# EMG_Sensors_Power.net
KiCad netlist of a schematic drawn in Altium Designer
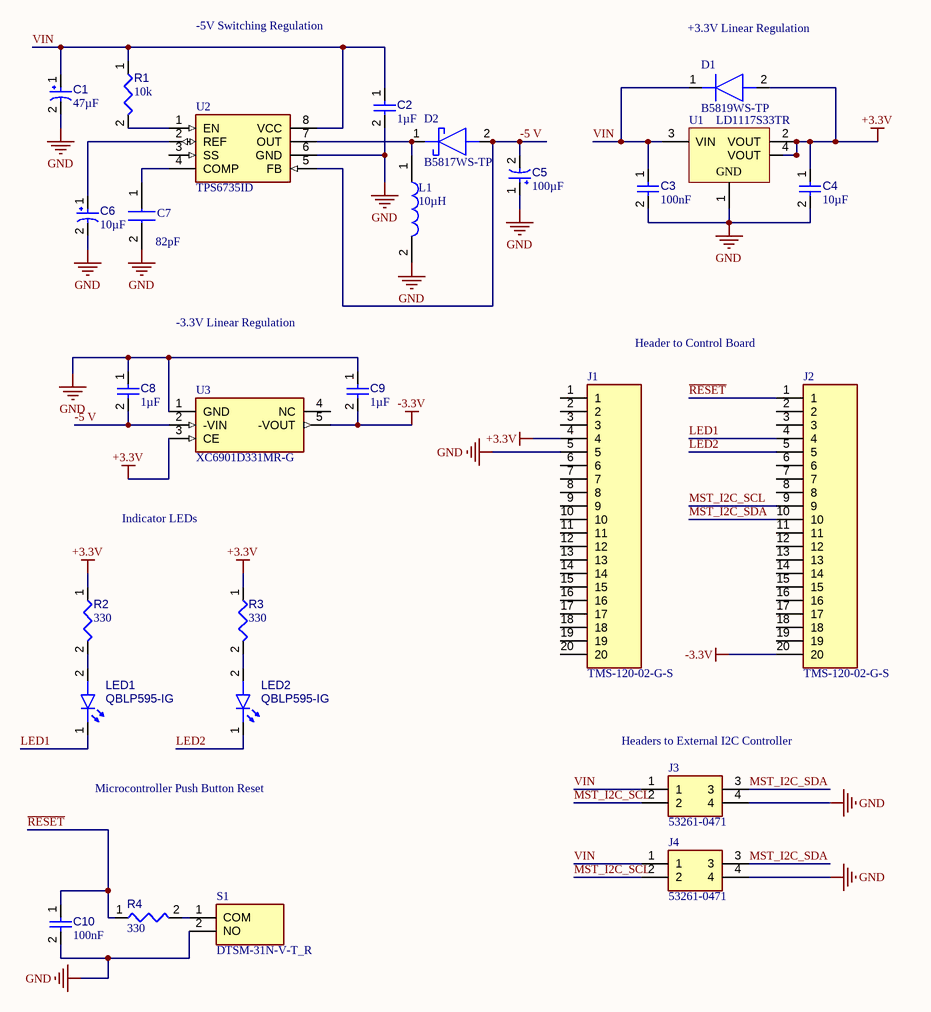
[diagram p0: EMG_Sensors_Power.SchDoc]

(export (version "E")
  (design (tool "Eeschema 10.0.6"))
  (components
    (comp (ref "C1")
      (value "47µF")
      (footprint "AVX-TAJ-C-2_L")
      (fields
        (field (name "TOLERANCE") "10%")
        (field (name "MANUFACTURER") "AVX")
        (field (name "Comment") "TAJC476K016RNJ")
      )
      (libsource (lib "Education") (part "CAP-P-2"))
    )
    (comp (ref "C2")
      (value "1µF")
      (footprint "CAPC1608X94X35NL15T15")
      (description "Chip Capacitor, 1 uF, +/- 10%, 16 V, 0603 (1608 Metric)")
      (fields (field (name "TOLERANCE") "10%") (field (name "Comment") "Capacitor 1 uF +/- 10% 16 V 0603"))
      (libsource (lib "Education") (part "CAP-NP-2"))
    )
    (comp (ref "C3")
      (value "100nF")
      (footprint "CAPC1005X56X25LL10T15")
      (description "Chip Capacitor, 0.1 uF, +/- 5%, 16 V, 0402 (1005 Metric)")
      (fields (field (name "TOLERANCE") "5%") (field (name "Comment") "Capacitor 0.1 uF +/- 5% 16 V 0402"))
      (libsource (lib "Education") (part "CAP-NP-2"))
    )
    (comp (ref "C4")
      (value "10µF")
      (footprint "CAPC2013X135X45NL10T25")
      (description "Chip Capacitor, 10 uF, +/- 10%, 16 V, 0805 (2012 Metric)")
      (fields (field (name "TOLERANCE") "10%") (field (name "Comment") "Capacitor 10 uF +/- 10% 16 V 0805"))
      (libsource (lib "Education") (part "CAP-NP-2"))
    )
    (comp (ref "C5")
      (value "100µF")
      (footprint "AVX-TAJ-C-2_L")
      (fields
        (field (name "TOLERANCE") "10%")
        (field (name "MANUFACTURER") "AVX")
        (field (name "Comment") "TAJC107K010RNJ")
      )
      (libsource (lib "") (part "CAP-P-2_1"))
    )
    (comp (ref "C6")
      (value "10µF")
      (footprint "CAPMP3217X18-T_V")
      (fields
        (field (name "TOLERANCE") "10%")
        (field (name "MANUFACTURER") "AVX")
        (field (name "Comment") "TAJA106K016RNJ")
      )
      (libsource (lib "Education") (part "CAP-P-2"))
    )
    (comp (ref "C7")
      (value "82pF")
      (footprint "SamacSys:CAPC0603X33N")
      (description "Capacitor 82pF  GRM0335C1H820JA01D")
      (fields (field (name "MANUFACTURER_PART_NUMBER") "GRM0335C1H820JA01D"))
      (libsource (lib "*") (part "GRM0335C1H820JA01D"))
    )
    (comp (ref "C8")
      (value "1µF")
      (footprint "CAPC1608X90X35ML15T15")
      (description "Chip Capacitor, 1 uF, +/- 10%, 16 V, 0603 (1608 Metric)")
      (fields (field (name "TOLERANCE") "10%") (field (name "Comment") "Capacitor 1uF +/- 10% 16V 0603"))
      (libsource (lib "Education") (part "CAP-NP-2"))
    )
    (comp (ref "C9")
      (value "1µF")
      (footprint "CAPC1608X90X35ML15T15")
      (description "Chip Capacitor, 1 uF, +/- 10%, 16 V, 0603 (1608 Metric)")
      (fields (field (name "TOLERANCE") "10%") (field (name "Comment") "Capacitor 1uF +/- 10% 16V 0603"))
      (libsource (lib "Education") (part "CAP-NP-2"))
    )
    (comp (ref "C10")
      (value "100nF")
      (footprint "CAPC1005X56X25LL10T15")
      (description "Chip Capacitor, 0.1 uF, +/- 5%, 16 V, 0402 (1005 Metric)")
      (fields (field (name "TOLERANCE") "5%") (field (name "Comment") "Capacitor 0.1 uF +/- 5% 16 V 0402"))
      (libsource (lib "Education") (part "CAP-NP-2"))
    )
    (comp (ref "D1")
      (value "B5819WS-TP")
      (footprint "SamacSys:SOD2512X115N")
      (description "Diode B5819WS-TP")
      (fields (field (name "MOUSER PART NUMBER") "833-B5819WS-TP"))
      (libsource (lib "*") (part "B5819WS-TP"))
    )
    (comp (ref "D2")
      (value "B5817WS-TP")
      (footprint "SamacSys:SOD2512X115N")
      (description "Schottky Diode B5817WS-TP")
      (fields (field (name "MOUSER PART NUMBER") "833-B5817WS-TP"))
      (libsource (lib "*") (part "B5817WS-TP"))
    )
    (comp (ref "J1")
      (value "TMS-120-02-G-S")
      (footprint "SamacSys:TMS-120-YY-XX-S")
      (description "Connector - female needed, place under board TMS-120-02-G-S")
      (fields (field (name "MOUSER PART NUMBER") "200-TMS12002GS"))
      (libsource (lib "*") (part "TMS-120-02-G-S"))
    )
    (comp (ref "J2")
      (value "TMS-120-02-G-S")
      (footprint "SamacSys:TMS-120-YY-XX-S")
      (description "Connector - female needed, place under board TMS-120-02-G-S")
      (fields (field (name "MOUSER PART NUMBER") "200-TMS12002GS"))
      (libsource (lib "*") (part "TMS-120-02-G-S"))
    )
    (comp (ref "J3")
      (value "53261-0471")
      (footprint "SamacSys:53261-0471")
      (description "Connector 53261-0471")
      (fields (field (name "MOUSER PART NUMBER") "538-53261-0471"))
      (libsource (lib "*") (part "53261-0471"))
    )
    (comp (ref "J4")
      (value "53261-0471")
      (footprint "SamacSys:53261-0471")
      (description "Connector 53261-0471")
      (fields (field (name "MOUSER PART NUMBER") "538-53261-0471"))
      (libsource (lib "*") (part "53261-0471"))
    )
    (comp (ref "L1")
      (value "10µH")
      (footprint "SamacSys:DO1608C")
      (description "Inductor 10µH DO1608C-103MLC")
      (fields
        (field (name "MANUFACTURER_PART_NUMBER") "DO1608C-103MLC")
        (field (name "MOUSER PART NUMBER") "994-DO1608C-103MLC")
      )
      (libsource (lib "*") (part "DO1608C-103MLC"))
    )
    (comp (ref "LED1")
      (value "QBLP595-IG")
      (footprint "QTB-QBLP595_V")
      (libsource (lib "Education") (part "LED-KA-2"))
    )
    (comp (ref "LED2")
      (value "QBLP595-IG")
      (footprint "QTB-QBLP595_V")
      (libsource (lib "Education") (part "LED-KA-2"))
    )
    (comp (ref "R1")
      (value "10k")
      (footprint "RESC1005X40X25ML05T05")
      (description "Chip Resistor, 10 KOhm, +/- 1%, 63 mW, -55 to 155 degC, 0402 (1005 Metric)")
      (fields (field (name "POWER") "63mW") (field (name "TOLERANCE") "1%"))
      (libsource (lib "Education") (part "RES-2"))
    )
    (comp (ref "R2")
      (value "330")
      (footprint "RESC0402(1005)_L")
      (description "Chip Resistor, 330 Ohms, +/-5 %, 63 mW, -55 to 155 degC, 0402")
      (fields (field (name "POWER") "63mW") (field (name "TOLERANCE") "5%"))
      (libsource (lib "Education") (part "RES-2"))
    )
    (comp (ref "R3")
      (value "330")
      (footprint "RESC0402(1005)_L")
      (description "Chip Resistor, 330 Ohms, +/-5 %, 63 mW, -55 to 155 degC, 0402")
      (fields (field (name "POWER") "63mW") (field (name "TOLERANCE") "5%"))
      (libsource (lib "Education") (part "RES-2"))
    )
    (comp (ref "R4")
      (value "330")
      (footprint "RESC0402(1005)_L")
      (description "Chip Resistor, 330 Ohms, +/-5 %, 63 mW, -55 to 155 degC, 0402")
      (fields (field (name "POWER") "63mW") (field (name "TOLERANCE") "5%"))
      (libsource (lib "Education") (part "RES-2"))
    )
    (comp (ref "S1")
      (value "DTSM-31N-V-T_R")
      (footprint "SamacSys:DTSM32NVTR")
      (description "Switch DTSM-31N-V-T_R")
      (fields
        (field (name "MANUFACTURER_PART_NUMBER") "DTSM-31N-V-T/R")
        (field (name "MOUSER PART NUMBER") "113-DTSM31NVTR")
      )
      (libsource (lib "SamacSys") (part "DTSM-31N-V-T_R"))
    )
    (comp (ref "U1")
      (value "LD1117S33TR")
      (footprint "SOT-223_L")
      (description "Fixed Low Drop Positive Voltage Regulator, 3.3V, 4-Pin SOT-223, Tape and Reel")
      (libsource (lib "Altium Content Vault") (part "PM-REG-LD1117-SOT4"))
    )
    (comp (ref "U2")
      (value "TPS6735ID")
      (footprint "SamacSys:SOIC127P600X175-8N")
      (description "Power Supply")
      (fields (field (name "MOUSER PART NUMBER") "595-TPS6735ID"))
      (libsource (lib "*") (part "TPS6735ID"))
    )
    (comp (ref "U3")
      (value "XC6901D331MR-G")
      (footprint "SamacSys:SOT95P280X130-5N")
      (description "Power Supply XC6901D331MR-G")
      (fields (field (name "MOUSER PART NUMBER") "865-XC6901D331MR-G"))
      (libsource (lib "*") (part "XC6901D331MR-G"))
    )
  )
  (nets
    (net (code "1") (name "+3.3V") (class "Default")
      (node (ref "C4") (pin "1") (pinfunction "1_1") (pintype "passive"))
      (node (ref "D1") (pin "2") (pinfunction "A_2") (pintype "passive"))
      (node (ref "J1") (pin "4") (pinfunction "4_4") (pintype "passive"))
      (node (ref "R2") (pin "1") (pinfunction "1_1") (pintype "passive"))
      (node (ref "R3") (pin "1") (pinfunction "1_1") (pintype "passive"))
      (node (ref "U1") (pin "2") (pinfunction "VOUT_2") (pintype "power_in"))
      (node (ref "U1") (pin "4") (pinfunction "VOUT_4") (pintype "power_in"))
      (node (ref "U3") (pin "3") (pinfunction "CE_3") (pintype "input"))
    )
    (net (code "2") (name "-3.3V") (class "Default")
      (node (ref "C9") (pin "2") (pinfunction "2_2") (pintype "passive"))
      (node (ref "J2") (pin "20") (pinfunction "20_20") (pintype "passive"))
      (node (ref "U3") (pin "5") (pinfunction "-VOUT_5") (pintype "output"))
    )
    (net (code "3") (name "/-5 V") (class "Default")
      (node (ref "C5") (pin "2") (pinfunction "2_2") (pintype "passive"))
      (node (ref "C8") (pin "2") (pinfunction "2_2") (pintype "passive"))
      (node (ref "D2") (pin "2") (pinfunction "A_2") (pintype "passive"))
      (node (ref "U2") (pin "5") (pinfunction "FB_5") (pintype "input"))
      (node (ref "U3") (pin "2") (pinfunction "-VIN_2") (pintype "input"))
    )
    (net (code "4") (name "/LED1") (class "Default")
      (node (ref "J2") (pin "4") (pinfunction "4_4") (pintype "passive"))
      (node (ref "LED1") (pin "1") (pinfunction "K_1") (pintype "passive"))
    )
    (net (code "5") (name "/LED2") (class "Default")
      (node (ref "J2") (pin "5") (pinfunction "5_5") (pintype "passive"))
      (node (ref "LED2") (pin "1") (pinfunction "K_1") (pintype "passive"))
    )
    (net (code "6") (name "/MST_I2C_SCL") (class "Default")
      (node (ref "J2") (pin "9") (pinfunction "9_9") (pintype "passive"))
      (node (ref "J3") (pin "2") (pinfunction "2_2") (pintype "passive"))
      (node (ref "J4") (pin "2") (pinfunction "2_2") (pintype "passive"))
    )
    (net (code "7") (name "/MST_I2C_SDA") (class "Default")
      (node (ref "J2") (pin "10") (pinfunction "10_10") (pintype "passive"))
      (node (ref "J3") (pin "3") (pinfunction "3_3") (pintype "passive"))
      (node (ref "J4") (pin "3") (pinfunction "3_3") (pintype "passive"))
    )
    (net (code "8") (name "/VIN") (class "Default")
      (node (ref "C1") (pin "1") (pinfunction "1_1") (pintype "passive"))
      (node (ref "C2") (pin "1") (pinfunction "1_1") (pintype "passive"))
      (node (ref "C3") (pin "1") (pinfunction "1_1") (pintype "passive"))
      (node (ref "D1") (pin "1") (pinfunction "K_1") (pintype "passive"))
      (node (ref "J3") (pin "1") (pinfunction "1_1") (pintype "passive"))
      (node (ref "J4") (pin "1") (pinfunction "1_1") (pintype "passive"))
      (node (ref "R1") (pin "1") (pinfunction "1_1") (pintype "passive"))
      (node (ref "U1") (pin "3") (pinfunction "VIN_3") (pintype "power_in"))
      (node (ref "U2") (pin "8") (pinfunction "VCC_8") (pintype "power_in"))
    )
    (net (code "9") (name "/~{RESET}") (class "Default")
      (node (ref "C10") (pin "1") (pinfunction "1_1") (pintype "passive"))
      (node (ref "J2") (pin "1") (pinfunction "1_1") (pintype "passive"))
      (node (ref "R4") (pin "1") (pinfunction "1_1") (pintype "passive"))
    )
    (net (code "10") (name "GND") (class "Default")
      (node (ref "C1") (pin "2") (pinfunction "2_2") (pintype "passive"))
      (node (ref "C10") (pin "2") (pinfunction "2_2") (pintype "passive"))
      (node (ref "C2") (pin "2") (pinfunction "2_2") (pintype "passive"))
      (node (ref "C3") (pin "2") (pinfunction "2_2") (pintype "passive"))
      (node (ref "C4") (pin "2") (pinfunction "2_2") (pintype "passive"))
      (node (ref "C5") (pin "1") (pinfunction "1_1") (pintype "passive"))
      (node (ref "C6") (pin "2") (pinfunction "2_2") (pintype "passive"))
      (node (ref "C7") (pin "2") (pinfunction "2_2") (pintype "passive"))
      (node (ref "C8") (pin "1") (pinfunction "1_1") (pintype "passive"))
      (node (ref "C9") (pin "1") (pinfunction "1_1") (pintype "passive"))
      (node (ref "J1") (pin "5") (pinfunction "5_5") (pintype "passive"))
      (node (ref "J3") (pin "4") (pinfunction "4_4") (pintype "passive"))
      (node (ref "J4") (pin "4") (pinfunction "4_4") (pintype "passive"))
      (node (ref "L1") (pin "2") (pinfunction "2_2") (pintype "passive"))
      (node (ref "S1") (pin "2") (pinfunction "NO_2") (pintype "passive"))
      (node (ref "U1") (pin "1") (pinfunction "GND_1") (pintype "power_in"))
      (node (ref "U2") (pin "6") (pinfunction "GND_6") (pintype "power_in"))
      (node (ref "U3") (pin "1") (pinfunction "GND_1") (pintype "power_in"))
    )
    (net (code "11") (name "Net-(D2-K)") (class "Default")
      (node (ref "D2") (pin "1") (pinfunction "K_1") (pintype "passive"))
      (node (ref "L1") (pin "1") (pinfunction "1_1") (pintype "passive"))
      (node (ref "U2") (pin "7") (pinfunction "OUT_7") (pintype "power_in"))
    )
    (net (code "12") (name "Net-(LED1-A)") (class "Default")
      (node (ref "LED1") (pin "2") (pinfunction "A_2") (pintype "passive"))
      (node (ref "R2") (pin "2") (pinfunction "2_2") (pintype "passive"))
    )
    (net (code "13") (name "Net-(LED2-A)") (class "Default")
      (node (ref "LED2") (pin "2") (pinfunction "A_2") (pintype "passive"))
      (node (ref "R3") (pin "2") (pinfunction "2_2") (pintype "passive"))
    )
    (net (code "14") (name "Net-(S1-COM)") (class "Default")
      (node (ref "R4") (pin "2") (pinfunction "2_2") (pintype "passive"))
      (node (ref "S1") (pin "1") (pinfunction "COM_1") (pintype "passive"))
    )
    (net (code "15") (name "Net-(U2-COMP)") (class "Default")
      (node (ref "C7") (pin "1") (pinfunction "1_1") (pintype "passive"))
      (node (ref "U2") (pin "4") (pinfunction "COMP_4") (pintype "passive"))
    )
    (net (code "16") (name "Net-(U2-EN)") (class "Default")
      (node (ref "R1") (pin "2") (pinfunction "2_2") (pintype "passive"))
      (node (ref "U2") (pin "1") (pinfunction "EN_1") (pintype "input"))
    )
    (net (code "17") (name "Net-(U2-REF)") (class "Default")
      (node (ref "C6") (pin "1") (pinfunction "1_1") (pintype "passive"))
      (node (ref "U2") (pin "2") (pinfunction "REF_2") (pintype "bidirectional"))
    )
    (net (code "18") (name "unconnected-(J1-Pad1)") (class "Default")
      (node (ref "J1") (pin "1") (pinfunction "1_1") (pintype "passive"))
    )
    (net (code "19") (name "unconnected-(J1-Pad2)") (class "Default")
      (node (ref "J1") (pin "2") (pinfunction "2_2") (pintype "passive"))
    )
    (net (code "20") (name "unconnected-(J1-Pad3)") (class "Default")
      (node (ref "J1") (pin "3") (pinfunction "3_3") (pintype "passive"))
    )
    (net (code "21") (name "unconnected-(J1-Pad6)") (class "Default")
      (node (ref "J1") (pin "6") (pinfunction "6_6") (pintype "passive"))
    )
    (net (code "22") (name "unconnected-(J1-Pad7)") (class "Default")
      (node (ref "J1") (pin "7") (pinfunction "7_7") (pintype "passive"))
    )
    (net (code "23") (name "unconnected-(J1-Pad8)") (class "Default")
      (node (ref "J1") (pin "8") (pinfunction "8_8") (pintype "passive"))
    )
    (net (code "24") (name "unconnected-(J1-Pad9)") (class "Default")
      (node (ref "J1") (pin "9") (pinfunction "9_9") (pintype "passive"))
    )
    (net (code "25") (name "unconnected-(J1-Pad10)") (class "Default")
      (node (ref "J1") (pin "10") (pinfunction "10_10") (pintype "passive"))
    )
    (net (code "26") (name "unconnected-(J1-Pad11)") (class "Default")
      (node (ref "J1") (pin "11") (pinfunction "11_11") (pintype "passive"))
    )
    (net (code "27") (name "unconnected-(J1-Pad12)") (class "Default")
      (node (ref "J1") (pin "12") (pinfunction "12_12") (pintype "passive"))
    )
    (net (code "28") (name "unconnected-(J1-Pad13)") (class "Default")
      (node (ref "J1") (pin "13") (pinfunction "13_13") (pintype "passive"))
    )
    (net (code "29") (name "unconnected-(J1-Pad14)") (class "Default")
      (node (ref "J1") (pin "14") (pinfunction "14_14") (pintype "passive"))
    )
    (net (code "30") (name "unconnected-(J1-Pad15)") (class "Default")
      (node (ref "J1") (pin "15") (pinfunction "15_15") (pintype "passive"))
    )
    (net (code "31") (name "unconnected-(J1-Pad16)") (class "Default")
      (node (ref "J1") (pin "16") (pinfunction "16_16") (pintype "passive"))
    )
    (net (code "32") (name "unconnected-(J1-Pad17)") (class "Default")
      (node (ref "J1") (pin "17") (pinfunction "17_17") (pintype "passive"))
    )
    (net (code "33") (name "unconnected-(J1-Pad18)") (class "Default")
      (node (ref "J1") (pin "18") (pinfunction "18_18") (pintype "passive"))
    )
    (net (code "34") (name "unconnected-(J1-Pad19)") (class "Default")
      (node (ref "J1") (pin "19") (pinfunction "19_19") (pintype "passive"))
    )
    (net (code "35") (name "unconnected-(J1-Pad20)") (class "Default")
      (node (ref "J1") (pin "20") (pinfunction "20_20") (pintype "passive"))
    )
    (net (code "36") (name "unconnected-(J2-Pad2)") (class "Default")
      (node (ref "J2") (pin "2") (pinfunction "2_2") (pintype "passive"))
    )
    (net (code "37") (name "unconnected-(J2-Pad3)") (class "Default")
      (node (ref "J2") (pin "3") (pinfunction "3_3") (pintype "passive"))
    )
    (net (code "38") (name "unconnected-(J2-Pad6)") (class "Default")
      (node (ref "J2") (pin "6") (pinfunction "6_6") (pintype "passive"))
    )
    (net (code "39") (name "unconnected-(J2-Pad7)") (class "Default")
      (node (ref "J2") (pin "7") (pinfunction "7_7") (pintype "passive"))
    )
    (net (code "40") (name "unconnected-(J2-Pad8)") (class "Default")
      (node (ref "J2") (pin "8") (pinfunction "8_8") (pintype "passive"))
    )
    (net (code "41") (name "unconnected-(J2-Pad11)") (class "Default")
      (node (ref "J2") (pin "11") (pinfunction "11_11") (pintype "passive"))
    )
    (net (code "42") (name "unconnected-(J2-Pad12)") (class "Default")
      (node (ref "J2") (pin "12") (pinfunction "12_12") (pintype "passive"))
    )
    (net (code "43") (name "unconnected-(J2-Pad13)") (class "Default")
      (node (ref "J2") (pin "13") (pinfunction "13_13") (pintype "passive"))
    )
    (net (code "44") (name "unconnected-(J2-Pad14)") (class "Default")
      (node (ref "J2") (pin "14") (pinfunction "14_14") (pintype "passive"))
    )
    (net (code "45") (name "unconnected-(J2-Pad15)") (class "Default")
      (node (ref "J2") (pin "15") (pinfunction "15_15") (pintype "passive"))
    )
    (net (code "46") (name "unconnected-(J2-Pad16)") (class "Default")
      (node (ref "J2") (pin "16") (pinfunction "16_16") (pintype "passive"))
    )
    (net (code "47") (name "unconnected-(J2-Pad17)") (class "Default")
      (node (ref "J2") (pin "17") (pinfunction "17_17") (pintype "passive"))
    )
    (net (code "48") (name "unconnected-(J2-Pad18)") (class "Default")
      (node (ref "J2") (pin "18") (pinfunction "18_18") (pintype "passive"))
    )
    (net (code "49") (name "unconnected-(J2-Pad19)") (class "Default")
      (node (ref "J2") (pin "19") (pinfunction "19_19") (pintype "passive"))
    )
    (net (code "50") (name "unconnected-(U2-SS-Pad3)") (class "Default")
      (node (ref "U2") (pin "3") (pinfunction "SS_3") (pintype "input"))
    )
    (net (code "51") (name "unconnected-(U3-NC-Pad4)") (class "Default")
      (node (ref "U3") (pin "4") (pinfunction "NC_4") (pintype "passive"))
    )
  )
)
